# microphone_stage.net
KiCad netlist of a schematic drawn in Altium Designer
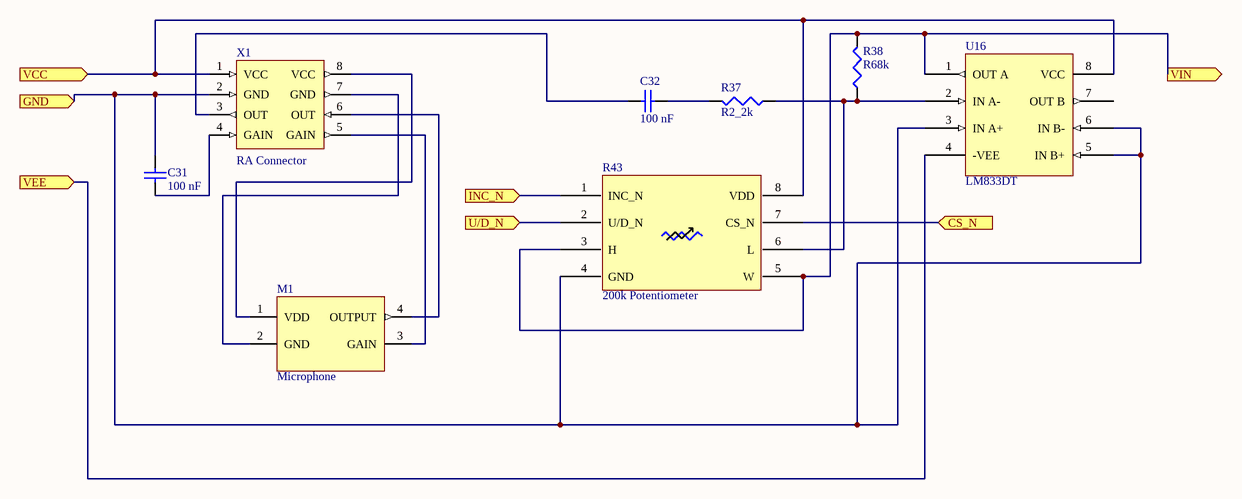
[diagram p0: microphone_stage.SchDoc]

(export (version "E")
  (design (tool "Eeschema 10.0.6"))
  (components
    (comp (ref "C31")
      (value "100 nF")
      (footprint "C0603")
      (description "100 nF Surface Mount Capacitor")
      (fields
        (field (name "MANUFACTURER") "Murata Electronics North America")
        (field (name "MANUFACTURER PART NUMBER") "GRM188R71C104KA01D")
      )
      (libsource (lib "Capstone Libraries") (part "C100nF"))
    )
    (comp (ref "C32")
      (value "100 nF")
      (footprint "C0603")
      (description "100 nF Surface Mount Capacitor")
      (fields
        (field (name "MANUFACTURER") "Murata Electronics North America")
        (field (name "MANUFACTURER PART NUMBER") "GRM188R71C104KA01D")
      )
      (libsource (lib "Capstone Libraries") (part "C100nF"))
    )
    (comp (ref "M1")
      (value "Microphone")
      (footprint "SPU0414HR5H-SB-7")
      (description "MIC MEMS ANALOG OMNI -22DB")
      (fields
        (field (name "MANUFACTURER") "Knowles")
        (field (name "MANUFACTURER PART NUMBER") "SPU0414HR5H-SB-7")
      )
      (libsource (lib "Capstone Libraries") (part "SPU0414HR5H-SB-7"))
    )
    (comp (ref "R37")
      (value "R2_2k")
      (footprint "R0603")
      (description "2.2k Ohms Surface Mount Resistor")
      (fields
        (field (name "MANUFACTURER") "Yageo")
        (field (name "MANUFACTURER PART NUMBER") "RC0603FR-072K2L")
      )
      (libsource (lib "Capstone Libraries") (part "R2_2k"))
    )
    (comp (ref "R38")
      (value "R68k")
      (footprint "R0603")
      (description "68k Ohms Surface Mount Resistor")
      (fields
        (field (name "MANUFACTURER") "Panasonic Electronic Components")
        (field (name "MANUFACTURER PART NUMBER") "ERJ-3EKF6802V")
      )
      (libsource (lib "Capstone Libraries") (part "R68k"))
    )
    (comp (ref "R43")
      (value "200k Potentiometer")
      (footprint "8-TSSOP")
      (description "200k Digital Potentiometer (32 Tap)")
      (fields
        (field (name "MANUFACTURER") "Maxim Integrated")
        (field (name "MANUFACTURER PART NUMBER") "MAX5160NEUA+")
      )
      (libsource (lib "Capstone Libraries") (part "MAX5160NEUA"))
    )
    (comp (ref "U16")
      (value "LM833DT")
      (footprint "soic8")
      (description "IC Dual Audio Amplifier")
      (fields (field (name "MANUFACTURER") "STMicroelectronics"))
      (libsource (lib "Capstone Libraries") (part "LM833DT"))
    )
    (comp (ref "X1")
      (value "RA Connector")
      (footprint "951104-7622-AR")
      (description "Right Angle Board-to-Board Connector")
      (fields (field (name "MANUFACTURER") "3M") (field (name "MANUFACTURER PART NUMBER") "951104-7622-AR"))
      (libsource (lib "Capstone Libraries") (part "HPM-06-02-T-S-RA"))
    )
  )
  (nets
    (net (code "1") (name "/CS_N") (class "Default")
      (node (ref "R43") (pin "7") (pinfunction "CS_N_7") (pintype "passive"))
    )
    (net (code "2") (name "/GND") (class "Default")
      (node (ref "C31") (pin "2") (pinfunction "2_2") (pintype "passive"))
      (node (ref "R43") (pin "4") (pinfunction "GND_4") (pintype "passive"))
      (node (ref "U16") (pin "3") (pinfunction "IN_A+_3") (pintype "input"))
      (node (ref "U16") (pin "5") (pinfunction "IN_B+_5") (pintype "input"))
      (node (ref "U16") (pin "6") (pinfunction "IN_B-_6") (pintype "input"))
      (node (ref "X1") (pin "2") (pinfunction "GND_2") (pintype "input"))
    )
    (net (code "3") (name "/INC_N") (class "Default")
      (node (ref "R43") (pin "1") (pinfunction "INC_N_1") (pintype "passive"))
    )
    (net (code "4") (name "/U{slash}D_N") (class "Default")
      (node (ref "R43") (pin "2") (pinfunction "U/D_N_2") (pintype "passive"))
    )
    (net (code "5") (name "/VCC") (class "Default")
      (node (ref "R43") (pin "8") (pinfunction "VDD_8") (pintype "passive"))
      (node (ref "U16") (pin "8") (pinfunction "VCC_8") (pintype "passive"))
      (node (ref "X1") (pin "1") (pinfunction "VCC_1") (pintype "input"))
    )
    (net (code "6") (name "/VEE") (class "Default")
      (node (ref "U16") (pin "4") (pinfunction "-VEE_4") (pintype "passive"))
    )
    (net (code "7") (name "/VIN") (class "Default")
      (node (ref "R38") (pin "2") (pinfunction "2_2") (pintype "passive"))
      (node (ref "R43") (pin "3") (pinfunction "H_3") (pintype "passive"))
      (node (ref "R43") (pin "5") (pinfunction "W_5") (pintype "passive"))
      (node (ref "U16") (pin "1") (pinfunction "OUT_A_1") (pintype "output"))
    )
    (net (code "8") (name "Net-(C31-Pad1)") (class "Default")
      (node (ref "C31") (pin "1") (pinfunction "1_1") (pintype "passive"))
      (node (ref "X1") (pin "4") (pinfunction "GAIN_4") (pintype "input"))
    )
    (net (code "9") (name "Net-(C32-Pad1)") (class "Default")
      (node (ref "C32") (pin "1") (pinfunction "1_1") (pintype "passive"))
      (node (ref "X1") (pin "3") (pinfunction "OUT_3") (pintype "output"))
    )
    (net (code "10") (name "Net-(C32-Pad2)") (class "Default")
      (node (ref "C32") (pin "2") (pinfunction "2_2") (pintype "passive"))
      (node (ref "R37") (pin "2") (pinfunction "2_2") (pintype "passive"))
    )
    (net (code "11") (name "Net-(M1-GAIN)") (class "Default")
      (node (ref "M1") (pin "3") (pinfunction "GAIN_3") (pintype "passive"))
      (node (ref "X1") (pin "5") (pinfunction "GAIN_5") (pintype "output"))
    )
    (net (code "12") (name "Net-(M1-GND)") (class "Default")
      (node (ref "M1") (pin "2") (pinfunction "GND_2") (pintype "passive"))
      (node (ref "X1") (pin "7") (pinfunction "GND_7") (pintype "output"))
    )
    (net (code "13") (name "Net-(M1-OUTPUT)") (class "Default")
      (node (ref "M1") (pin "4") (pinfunction "OUTPUT_4") (pintype "output"))
      (node (ref "X1") (pin "6") (pinfunction "OUT_6") (pintype "input"))
    )
    (net (code "14") (name "Net-(M1-VDD)") (class "Default")
      (node (ref "M1") (pin "1") (pinfunction "VDD_1") (pintype "passive"))
      (node (ref "X1") (pin "8") (pinfunction "VCC_8") (pintype "output"))
    )
    (net (code "15") (name "Net-(R43-L)") (class "Default")
      (node (ref "R37") (pin "1") (pinfunction "1_1") (pintype "passive"))
      (node (ref "R38") (pin "1") (pinfunction "1_1") (pintype "passive"))
      (node (ref "R43") (pin "6") (pinfunction "L_6") (pintype "passive"))
      (node (ref "U16") (pin "2") (pinfunction "IN_A-_2") (pintype "input"))
    )
    (net (code "16") (name "unconnected-(U16-OUT_B-Pad7)") (class "Default")
      (node (ref "U16") (pin "7") (pinfunction "OUT_B_7") (pintype "output"))
    )
  )
)
